# WS2812B-HueStrip.net
KiCad netlist of a schematic drawn in EAGLE
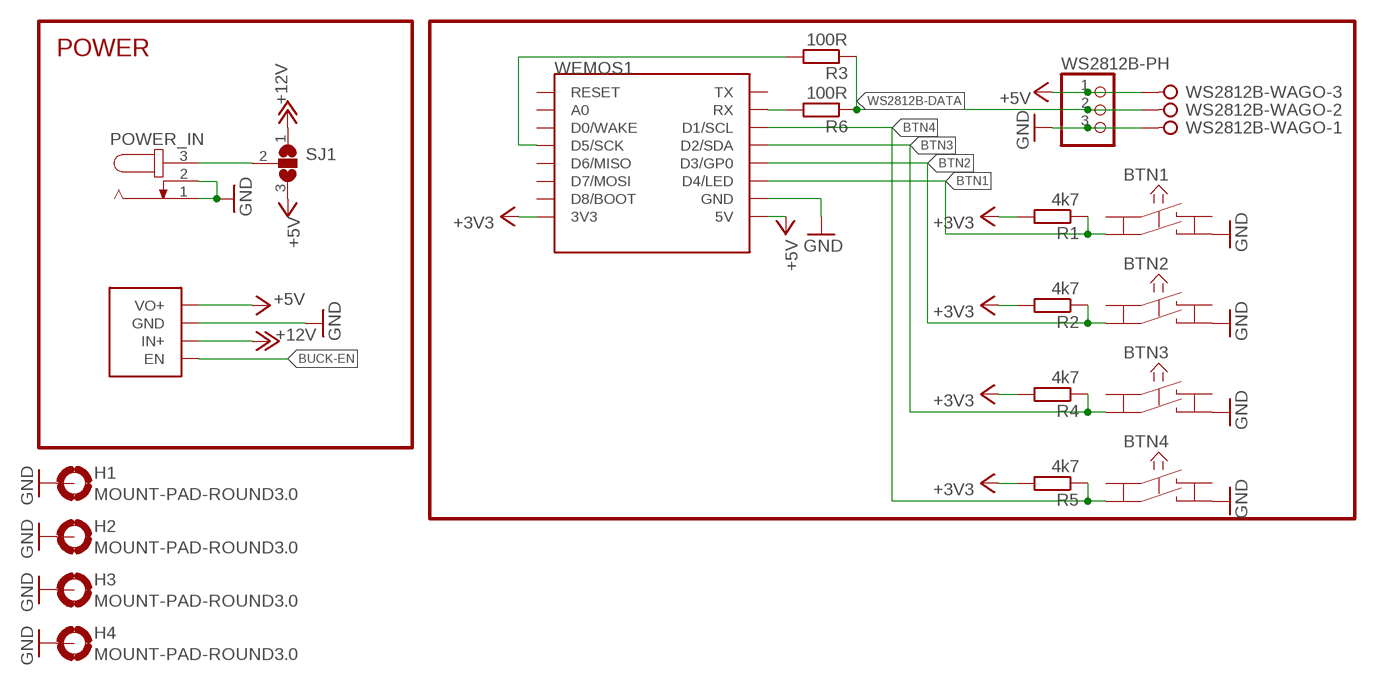
[diagram p0: schematic, sheet 1]

(export (version "E")
  (design (tool "Eeschema 10.0.6"))
  (components
    (comp (ref "BTN1")
      (value "KSM611A")
      (footprint "eagle-import:KSM611A")
      (libsource (lib "eagle-import") (part "KSM611A"))
    )
    (comp (ref "BTN2")
      (value "KSM611A")
      (footprint "eagle-import:KSM611A")
      (libsource (lib "eagle-import") (part "KSM611A"))
    )
    (comp (ref "BTN3")
      (value "KSM611A")
      (footprint "eagle-import:KSM611A")
      (libsource (lib "eagle-import") (part "KSM611A"))
    )
    (comp (ref "BTN4")
      (value "KSM611A")
      (footprint "eagle-import:KSM611A")
      (libsource (lib "eagle-import") (part "KSM611A"))
    )
    (comp (ref "H1")
      (value "MOUNT-PAD-ROUND3.0")
      (footprint "eagle-import:3,0-PAD")
      (libsource (lib "eagle-import") (part "MOUNT-PAD-ROUND3.0"))
    )
    (comp (ref "H2")
      (value "MOUNT-PAD-ROUND3.0")
      (footprint "eagle-import:3,0-PAD")
      (libsource (lib "eagle-import") (part "MOUNT-PAD-ROUND3.0"))
    )
    (comp (ref "H3")
      (value "MOUNT-PAD-ROUND3.0")
      (footprint "eagle-import:3,0-PAD")
      (libsource (lib "eagle-import") (part "MOUNT-PAD-ROUND3.0"))
    )
    (comp (ref "H4")
      (value "MOUNT-PAD-ROUND3.0")
      (footprint "eagle-import:3,0-PAD")
      (libsource (lib "eagle-import") (part "MOUNT-PAD-ROUND3.0"))
    )
    (comp (ref "POWER_IN")
      (value "RAPC7120")
      (footprint "eagle-import:RAPC712")
      (libsource (lib "eagle-import") (part "RAPC7120"))
    )
    (comp (ref "R1")
      (value "4k7")
      (footprint "eagle-import:MULTI_RESISTOR")
      (libsource (lib "eagle-import") (part "R-EU_MULTI"))
    )
    (comp (ref "R2")
      (value "4k7")
      (footprint "eagle-import:MULTI_RESISTOR")
      (libsource (lib "eagle-import") (part "R-EU_MULTI"))
    )
    (comp (ref "R3")
      (value "100R")
      (footprint "eagle-import:MULTI_RESISTOR")
      (libsource (lib "eagle-import") (part "R-EU_MULTI"))
    )
    (comp (ref "R4")
      (value "4k7")
      (footprint "eagle-import:MULTI_RESISTOR")
      (libsource (lib "eagle-import") (part "R-EU_MULTI"))
    )
    (comp (ref "R5")
      (value "4k7")
      (footprint "eagle-import:MULTI_RESISTOR")
      (libsource (lib "eagle-import") (part "R-EU_MULTI"))
    )
    (comp (ref "R6")
      (value "100R")
      (footprint "eagle-import:MULTI_RESISTOR")
      (libsource (lib "eagle-import") (part "R-EU_MULTI"))
    )
    (comp (ref "SJ1")
      (value "SJ2WW")
      (footprint "eagle-import:SJ_2W")
      (libsource (lib "eagle-import") (part "SJ2WW"))
    )
    (comp (ref "U$1")
      (value "BUCK_CONVERTER_TE818")
      (footprint "eagle-import:BUCK_CONVERTER_TE818")
      (libsource (lib "eagle-import") (part "BUCK_CONVERTER_TE818"))
    )
    (comp (ref "WEMOS1")
      (value "WEMOS-D1-MINI")
      (footprint "eagle-import:WEMOS-D1-MINI")
      (libsource (lib "eagle-import") (part "WEMOS-D1-MINI"))
    )
    (comp (ref "WS2812B-PH")
      (value "PINHD-1X03_2.54-S")
      (footprint "eagle-import:1X03-S")
      (libsource (lib "eagle-import") (part "PINHD-1X03_2.54-S"))
    )
    (comp (ref "WS2812B-WAGO")
      (value "W237-3E")
      (footprint "eagle-import:W237-3E")
      (libsource (lib "eagle-import") (part "W237-3E"))
    )
  )
  (nets
    (net (code "1") (name "+3V3") (class "Default")
      (node (ref "R1") (pin "2@1") (pinfunction "2_2@1") (pintype "passive"))
      (node (ref "R1") (pin "2@2") (pinfunction "2_2@2") (pintype "passive"))
      (node (ref "R2") (pin "2@1") (pinfunction "2_2@1") (pintype "passive"))
      (node (ref "R2") (pin "2@2") (pinfunction "2_2@2") (pintype "passive"))
      (node (ref "R4") (pin "2@1") (pinfunction "2_2@1") (pintype "passive"))
      (node (ref "R4") (pin "2@2") (pinfunction "2_2@2") (pintype "passive"))
      (node (ref "R5") (pin "2@1") (pinfunction "2_2@1") (pintype "passive"))
      (node (ref "R5") (pin "2@2") (pinfunction "2_2@2") (pintype "passive"))
      (node (ref "WEMOS1") (pin "3V3") (pinfunction "3V3_3V3") (pintype "bidirectional"))
    )
    (net (code "2") (name "+5V") (class "Default")
      (node (ref "SJ1") (pin "3") (pinfunction "3_3") (pintype "passive"))
      (node (ref "U$1") (pin "VO+") (pinfunction "VO+_VO+") (pintype "bidirectional"))
      (node (ref "WEMOS1") (pin "5V") (pinfunction "5V_5V") (pintype "bidirectional"))
      (node (ref "WS2812B-PH") (pin "1") (pinfunction "1_1") (pintype "passive"))
      (node (ref "WS2812B-WAGO") (pin "3") (pinfunction "KL_3") (pintype "passive"))
    )
    (net (code "3") (name "+12V") (class "Default")
      (node (ref "SJ1") (pin "1") (pinfunction "1_1") (pintype "passive"))
      (node (ref "U$1") (pin "IN+") (pinfunction "IN+_IN+") (pintype "bidirectional"))
    )
    (net (code "4") (name "BTN1") (class "Default")
      (node (ref "BTN1") (pin "C") (pinfunction "C_C") (pintype "passive"))
      (node (ref "R1") (pin "1@1") (pinfunction "1_1@1") (pintype "passive"))
      (node (ref "R1") (pin "1@2") (pinfunction "1_1@2") (pintype "passive"))
      (node (ref "WEMOS1") (pin "D4") (pinfunction "D4/LED_D4") (pintype "bidirectional"))
    )
    (net (code "5") (name "BTN2") (class "Default")
      (node (ref "BTN2") (pin "C") (pinfunction "C_C") (pintype "passive"))
      (node (ref "R2") (pin "1@1") (pinfunction "1_1@1") (pintype "passive"))
      (node (ref "R2") (pin "1@2") (pinfunction "1_1@2") (pintype "passive"))
      (node (ref "WEMOS1") (pin "D3") (pinfunction "D3/GP0_D3") (pintype "bidirectional"))
    )
    (net (code "6") (name "BTN3") (class "Default")
      (node (ref "BTN3") (pin "C") (pinfunction "C_C") (pintype "passive"))
      (node (ref "R4") (pin "1@1") (pinfunction "1_1@1") (pintype "passive"))
      (node (ref "R4") (pin "1@2") (pinfunction "1_1@2") (pintype "passive"))
      (node (ref "WEMOS1") (pin "D2") (pinfunction "D2/SDA_D2") (pintype "bidirectional"))
    )
    (net (code "7") (name "BTN4") (class "Default")
      (node (ref "BTN4") (pin "C") (pinfunction "C_C") (pintype "passive"))
      (node (ref "R5") (pin "1@1") (pinfunction "1_1@1") (pintype "passive"))
      (node (ref "R5") (pin "1@2") (pinfunction "1_1@2") (pintype "passive"))
      (node (ref "WEMOS1") (pin "D1") (pinfunction "D1/SCL_D1") (pintype "bidirectional"))
    )
    (net (code "8") (name "BUCK-EN") (class "Default")
      (node (ref "U$1") (pin "EN") (pinfunction "EN_EN") (pintype "bidirectional"))
    )
    (net (code "9") (name "GND") (class "Default")
      (node (ref "BTN1") (pin "D") (pinfunction "D_D") (pintype "passive"))
      (node (ref "BTN2") (pin "D") (pinfunction "D_D") (pintype "passive"))
      (node (ref "BTN3") (pin "D") (pinfunction "D_D") (pintype "passive"))
      (node (ref "BTN4") (pin "D") (pinfunction "D_D") (pintype "passive"))
      (node (ref "H1") (pin "B3,0") (pinfunction "MOUNT_B3,0") (pintype "passive"))
      (node (ref "H2") (pin "B3,0") (pinfunction "MOUNT_B3,0") (pintype "passive"))
      (node (ref "H3") (pin "B3,0") (pinfunction "MOUNT_B3,0") (pintype "passive"))
      (node (ref "H4") (pin "B3,0") (pinfunction "MOUNT_B3,0") (pintype "passive"))
      (node (ref "POWER_IN") (pin "1") (pinfunction "1_1") (pintype "passive"))
      (node (ref "POWER_IN") (pin "2") (pinfunction "2_2") (pintype "passive"))
      (node (ref "U$1") (pin "GND") (pinfunction "GND_GND") (pintype "bidirectional"))
      (node (ref "WEMOS1") (pin "GND") (pinfunction "GND_GND") (pintype "bidirectional"))
      (node (ref "WS2812B-PH") (pin "3") (pinfunction "3_3") (pintype "passive"))
      (node (ref "WS2812B-WAGO") (pin "1") (pinfunction "KL_1") (pintype "passive"))
    )
    (net (code "10") (name "Net-(POWER_IN-Pad3)") (class "Default")
      (node (ref "POWER_IN") (pin "3") (pinfunction "3_3") (pintype "passive"))
      (node (ref "SJ1") (pin "2") (pinfunction "2_2") (pintype "passive"))
    )
    (net (code "11") (name "Net-(R6-2-Pad2@1)") (class "Default")
      (node (ref "R6") (pin "2@1") (pinfunction "2_2@1") (pintype "passive"))
      (node (ref "R6") (pin "2@2") (pinfunction "2_2@2") (pintype "passive"))
      (node (ref "WEMOS1") (pin "RX") (pinfunction "RX_RX") (pintype "bidirectional"))
    )
    (net (code "12") (name "Net-(WEMOS1-D5{slash}SCK)") (class "Default")
      (node (ref "R3") (pin "2@1") (pinfunction "2_2@1") (pintype "passive"))
      (node (ref "R3") (pin "2@2") (pinfunction "2_2@2") (pintype "passive"))
      (node (ref "WEMOS1") (pin "D5") (pinfunction "D5/SCK_D5") (pintype "bidirectional"))
    )
    (net (code "13") (name "WS2812B-DATA") (class "Default")
      (node (ref "R3") (pin "1@1") (pinfunction "1_1@1") (pintype "passive"))
      (node (ref "R3") (pin "1@2") (pinfunction "1_1@2") (pintype "passive"))
      (node (ref "R6") (pin "1@1") (pinfunction "1_1@1") (pintype "passive"))
      (node (ref "R6") (pin "1@2") (pinfunction "1_1@2") (pintype "passive"))
      (node (ref "WS2812B-PH") (pin "2") (pinfunction "2_2") (pintype "passive"))
      (node (ref "WS2812B-WAGO") (pin "2") (pinfunction "KL_2") (pintype "passive"))
    )
    (net (code "14") (name "unconnected-(BTN1-PadA)") (class "Default")
      (node (ref "BTN1") (pin "A") (pinfunction "A_A") (pintype "passive"))
    )
    (net (code "15") (name "unconnected-(BTN1-PadB)") (class "Default")
      (node (ref "BTN1") (pin "B") (pinfunction "B_B") (pintype "passive"))
    )
    (net (code "16") (name "unconnected-(BTN2-PadA)") (class "Default")
      (node (ref "BTN2") (pin "A") (pinfunction "A_A") (pintype "passive"))
    )
    (net (code "17") (name "unconnected-(BTN2-PadB)") (class "Default")
      (node (ref "BTN2") (pin "B") (pinfunction "B_B") (pintype "passive"))
    )
    (net (code "18") (name "unconnected-(BTN3-PadA)") (class "Default")
      (node (ref "BTN3") (pin "A") (pinfunction "A_A") (pintype "passive"))
    )
    (net (code "19") (name "unconnected-(BTN3-PadB)") (class "Default")
      (node (ref "BTN3") (pin "B") (pinfunction "B_B") (pintype "passive"))
    )
    (net (code "20") (name "unconnected-(BTN4-PadA)") (class "Default")
      (node (ref "BTN4") (pin "A") (pinfunction "A_A") (pintype "passive"))
    )
    (net (code "21") (name "unconnected-(BTN4-PadB)") (class "Default")
      (node (ref "BTN4") (pin "B") (pinfunction "B_B") (pintype "passive"))
    )
    (net (code "22") (name "unconnected-(WEMOS1-D0{slash}WAKE-PadD0)") (class "Default")
      (node (ref "WEMOS1") (pin "D0") (pinfunction "D0/WAKE_D0") (pintype "bidirectional"))
    )
    (net (code "23") (name "unconnected-(WEMOS1-D6{slash}MISO-PadD6)") (class "Default")
      (node (ref "WEMOS1") (pin "D6") (pinfunction "D6/MISO_D6") (pintype "bidirectional"))
    )
    (net (code "24") (name "unconnected-(WEMOS1-D7{slash}MOSI-PadD7)") (class "Default")
      (node (ref "WEMOS1") (pin "D7") (pinfunction "D7/MOSI_D7") (pintype "bidirectional"))
    )
    (net (code "25") (name "unconnected-(WEMOS1-D8{slash}BOOT-PadD8)") (class "Default")
      (node (ref "WEMOS1") (pin "D8") (pinfunction "D8/BOOT_D8") (pintype "bidirectional"))
    )
    (net (code "26") (name "unconnected-(WEMOS1-PadA0)") (class "Default")
      (node (ref "WEMOS1") (pin "A0") (pinfunction "A0_A0") (pintype "bidirectional"))
    )
    (net (code "27") (name "unconnected-(WEMOS1-PadRESET)") (class "Default")
      (node (ref "WEMOS1") (pin "RESET") (pinfunction "RESET_RESET") (pintype "bidirectional"))
    )
    (net (code "28") (name "unconnected-(WEMOS1-PadTX)") (class "Default")
      (node (ref "WEMOS1") (pin "TX") (pinfunction "TX_TX") (pintype "bidirectional"))
    )
  )
)
